# esquemacamiseta1.net
KiCad netlist of a schematic drawn in EAGLE
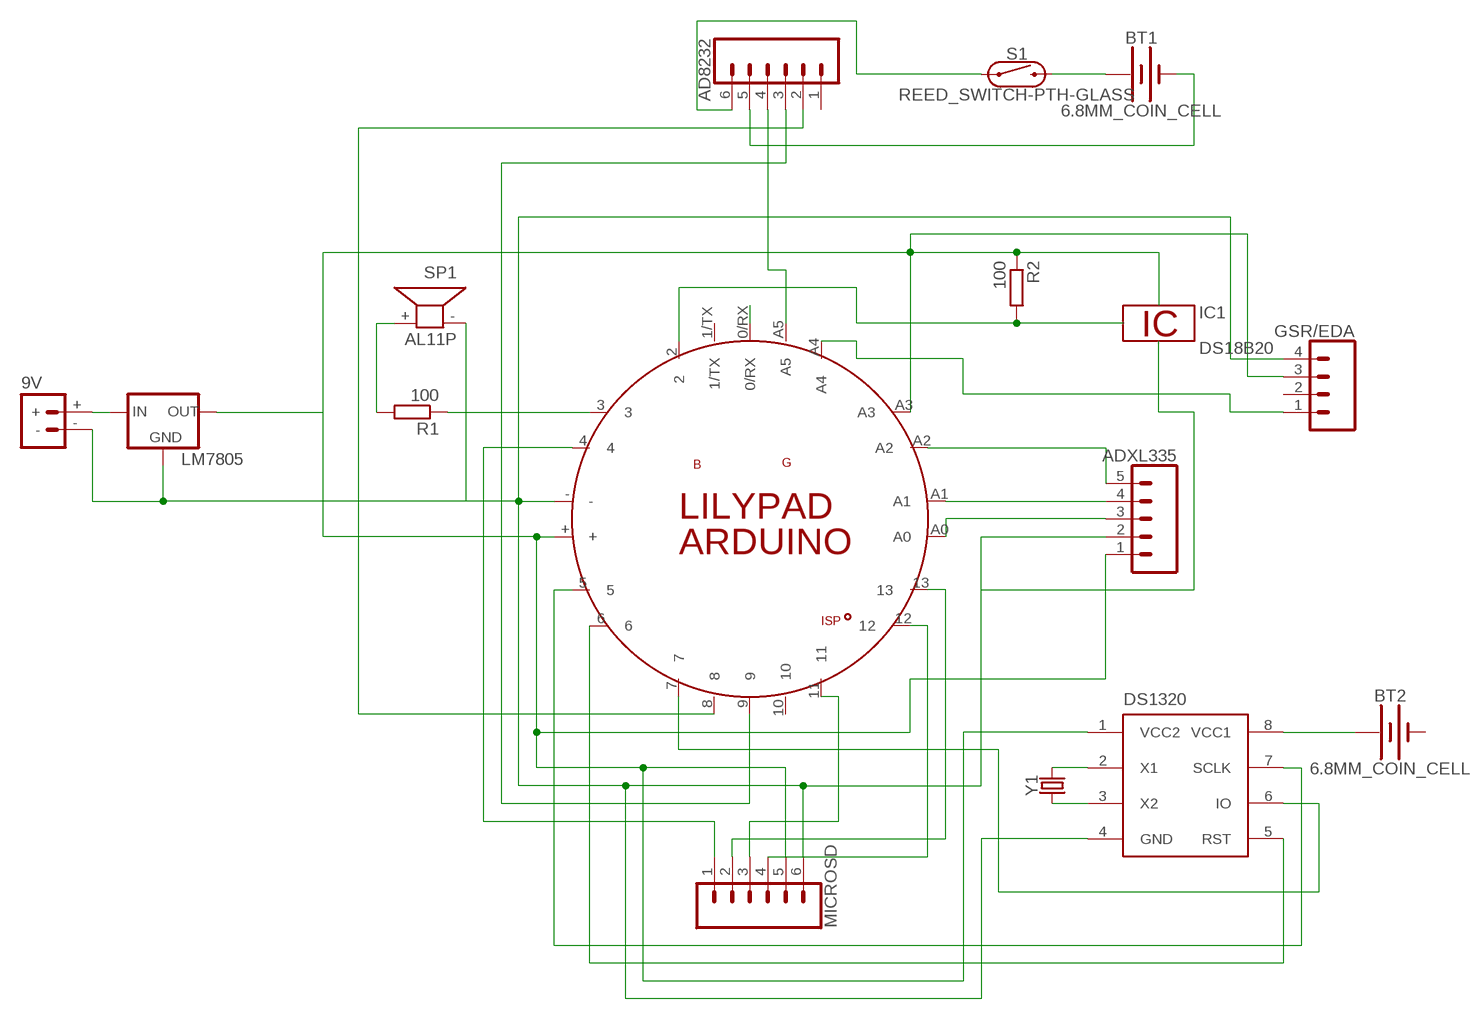
[diagram p0: schematic, sheet 1]

(export (version "E")
  (design (tool "Eeschema 10.0.6"))
  (components
    (comp (ref "9V")
      (value "BATTERY_CONN_DEANS")
      (footprint "eagle-import:DEANS")
      (libsource (lib "eagle-import") (part "BATTERY_CONN_DEANS"))
    )
    (comp (ref "AD8232")
      (value "CONN_06FEMALE_LOCK")
      (footprint "eagle-import:1X06_FEMALE_LOCK.010")
      (libsource (lib "eagle-import") (part "CONN_06FEMALE_LOCK"))
    )
    (comp (ref "ADXL335")
      (value "CONN_05")
      (footprint "eagle-import:1X05")
      (libsource (lib "eagle-import") (part "CONN_05"))
    )
    (comp (ref "BT1")
      (value "6.8MM_COIN_CELL")
      (footprint "eagle-import:BATTCON-6.8MM")
      (libsource (lib "eagle-import") (part "BATTERY-6.8MM_SMD"))
    )
    (comp (ref "BT2")
      (value "6.8MM_COIN_CELL")
      (footprint "eagle-import:BATTCON-6.8MM")
      (libsource (lib "eagle-import") (part "BATTERY-6.8MM_SMD"))
    )
    (comp (ref "DS1320")
      (value "DS1302")
      (footprint "eagle-import:PDIP8")
      (libsource (lib "eagle-import") (part "DS1302"))
    )
    (comp (ref "GSR/EDA")
      (value "CONN_04JST-PTH")
      (footprint "eagle-import:JST-4-PTH")
      (libsource (lib "eagle-import") (part "CONN_04JST-PTH"))
    )
    (comp (ref "IC1")
      (value "DS18B20")
      (footprint "eagle-import:TO92-")
      (libsource (lib "eagle-import") (part "DS18B20"))
    )
    (comp (ref "LM7805")
      (value "V_REG_78XX-TO-220")
      (footprint "eagle-import:TO-220-ALT")
      (libsource (lib "eagle-import") (part "V_REG_78XX-TO-220"))
    )
    (comp (ref "MICROSD")
      (value "CONN_06FEMALE_LOCK")
      (footprint "eagle-import:1X06_FEMALE_LOCK.010")
      (libsource (lib "eagle-import") (part "CONN_06FEMALE_LOCK"))
    )
    (comp (ref "PCB1")
      (value "ARDUINO_LILYPAD")
      (footprint "eagle-import:ARDUINO_LILYPAD")
      (libsource (lib "eagle-import") (part "ARDUINO_LILYPAD"))
    )
    (comp (ref "R1")
      (value "100")
      (footprint "eagle-import:0309_12")
      (libsource (lib "eagle-import") (part "R-EU_0309/12"))
    )
    (comp (ref "R2")
      (value "100")
      (footprint "eagle-import:0309_12")
      (libsource (lib "eagle-import") (part "R-EU_0309/12"))
    )
    (comp (ref "S1")
      (value "REED_SWITCH-PTH-GLASS")
      (footprint "eagle-import:REED_SWITCH_GLASS")
      (libsource (lib "eagle-import") (part "REED_SWITCH-PTH-GLASS"))
    )
    (comp (ref "SP1")
      (value "AL11P")
      (footprint "eagle-import:AL11P")
      (libsource (lib "eagle-import") (part "AL11P"))
    )
    (comp (ref "Y1")
      (value "CRYSTALPTH-2X6")
      (footprint "eagle-import:CRYSTAL-PTH-2X6-CYL")
      (libsource (lib "eagle-import") (part "CRYSTALPTH-2X6"))
    )
  )
  (nets
    (net (code "1") (name "/-") (class "Default")
      (node (ref "BT2") (pin "-") (pinfunction "-_-") (pintype "power_in"))
    )
    (net (code "2") (name "Net-(9V-Pad+)") (class "Default")
      (node (ref "9V") (pin "+") (pinfunction "+_+") (pintype "passive"))
      (node (ref "LM7805") (pin "IN") (pinfunction "IN_IN") (pintype "input"))
    )
    (net (code "3") (name "Net-(AD8232-Pad2)") (class "Default")
      (node (ref "AD8232") (pin "2") (pinfunction "2_2") (pintype "passive"))
      (node (ref "PCB1") (pin "8") (pinfunction "8_8") (pintype "bidirectional"))
    )
    (net (code "4") (name "Net-(AD8232-Pad3)") (class "Default")
      (node (ref "AD8232") (pin "3") (pinfunction "3_3") (pintype "passive"))
      (node (ref "PCB1") (pin "9") (pinfunction "9_9") (pintype "bidirectional"))
    )
    (net (code "5") (name "Net-(AD8232-Pad4)") (class "Default")
      (node (ref "AD8232") (pin "4") (pinfunction "4_4") (pintype "passive"))
      (node (ref "PCB1") (pin "A5") (pinfunction "A5_A5") (pintype "bidirectional"))
    )
    (net (code "6") (name "Net-(AD8232-Pad5)") (class "Default")
      (node (ref "AD8232") (pin "5") (pinfunction "5_5") (pintype "passive"))
      (node (ref "BT1") (pin "-") (pinfunction "-_-") (pintype "power_in"))
    )
    (net (code "7") (name "Net-(ADXL335-Pad3)") (class "Default")
      (node (ref "ADXL335") (pin "3") (pinfunction "3_3") (pintype "passive"))
      (node (ref "PCB1") (pin "A0") (pinfunction "A0_A0") (pintype "bidirectional"))
    )
    (net (code "8") (name "Net-(ADXL335-Pad4)") (class "Default")
      (node (ref "ADXL335") (pin "4") (pinfunction "4_4") (pintype "passive"))
      (node (ref "PCB1") (pin "A1") (pinfunction "A1_A1") (pintype "bidirectional"))
    )
    (net (code "9") (name "Net-(ADXL335-Pad5)") (class "Default")
      (node (ref "ADXL335") (pin "5") (pinfunction "5_5") (pintype "passive"))
      (node (ref "PCB1") (pin "A2") (pinfunction "A2_A2") (pintype "bidirectional"))
    )
    (net (code "10") (name "Net-(DS1320-GND)") (class "Default")
      (node (ref "9V") (pin "-") (pinfunction "-_-") (pintype "passive"))
      (node (ref "ADXL335") (pin "2") (pinfunction "2_2") (pintype "passive"))
      (node (ref "DS1320") (pin "4") (pinfunction "GND_4") (pintype "power_in"))
      (node (ref "GSR/EDA") (pin "4") (pinfunction "4_4") (pintype "passive"))
      (node (ref "LM7805") (pin "GND") (pinfunction "GND_GND") (pintype "input"))
      (node (ref "MICROSD") (pin "6") (pinfunction "6_6") (pintype "passive"))
      (node (ref "PCB1") (pin "-") (pinfunction "-_-") (pintype "bidirectional"))
      (node (ref "SP1") (pin "-") (pinfunction "1_-") (pintype "passive"))
    )
    (net (code "11") (name "Net-(DS1320-IO)") (class "Default")
      (node (ref "DS1320") (pin "6") (pinfunction "IO_6") (pintype "bidirectional"))
      (node (ref "PCB1") (pin "7") (pinfunction "7_7") (pintype "bidirectional"))
    )
    (net (code "12") (name "Net-(DS1320-RST)") (class "Default")
      (node (ref "DS1320") (pin "5") (pinfunction "RST_5") (pintype "input"))
      (node (ref "PCB1") (pin "6") (pinfunction "6_6") (pintype "bidirectional"))
    )
    (net (code "13") (name "Net-(DS1320-SCLK)") (class "Default")
      (node (ref "DS1320") (pin "7") (pinfunction "SCLK_7") (pintype "input"))
      (node (ref "PCB1") (pin "5") (pinfunction "5_5") (pintype "bidirectional"))
    )
    (net (code "14") (name "Net-(DS1320-VCC1)") (class "Default")
      (node (ref "BT2") (pin "+") (pinfunction "+_+") (pintype "power_in"))
      (node (ref "DS1320") (pin "8") (pinfunction "VCC1_8") (pintype "power_in"))
    )
    (net (code "15") (name "Net-(DS1320-VCC2)") (class "Default")
      (node (ref "ADXL335") (pin "1") (pinfunction "1_1") (pintype "passive"))
      (node (ref "DS1320") (pin "1") (pinfunction "VCC2_1") (pintype "power_in"))
      (node (ref "GSR/EDA") (pin "3") (pinfunction "3_3") (pintype "passive"))
      (node (ref "MICROSD") (pin "5") (pinfunction "5_5") (pintype "passive"))
      (node (ref "PCB1") (pin "+") (pinfunction "+_+") (pintype "bidirectional"))
      (node (ref "PCB1") (pin "A3") (pinfunction "A3_A3") (pintype "bidirectional"))
      (node (ref "R2") (pin "1") (pinfunction "1_1") (pintype "passive"))
    )
    (net (code "16") (name "Net-(DS1320-X1)") (class "Default")
      (node (ref "DS1320") (pin "2") (pinfunction "X1_2") (pintype "bidirectional"))
      (node (ref "Y1") (pin "2") (pinfunction "2_2") (pintype "passive"))
    )
    (net (code "17") (name "Net-(DS1320-X2)") (class "Default")
      (node (ref "DS1320") (pin "3") (pinfunction "X2_3") (pintype "bidirectional"))
      (node (ref "Y1") (pin "1") (pinfunction "1_1") (pintype "passive"))
    )
    (net (code "18") (name "Net-(GSR/EDA-Pad1)") (class "Default")
      (node (ref "GSR/EDA") (pin "1") (pinfunction "1_1") (pintype "passive"))
      (node (ref "PCB1") (pin "A4") (pinfunction "A4_A4") (pintype "bidirectional"))
    )
    (net (code "19") (name "Net-(MICROSD-Pad1)") (class "Default")
      (node (ref "MICROSD") (pin "1") (pinfunction "1_1") (pintype "passive"))
      (node (ref "PCB1") (pin "4") (pinfunction "4_4") (pintype "bidirectional"))
    )
    (net (code "20") (name "Net-(MICROSD-Pad2)") (class "Default")
      (node (ref "MICROSD") (pin "2") (pinfunction "2_2") (pintype "passive"))
      (node (ref "PCB1") (pin "13") (pinfunction "13_13") (pintype "bidirectional"))
    )
    (net (code "21") (name "Net-(MICROSD-Pad3)") (class "Default")
      (node (ref "MICROSD") (pin "3") (pinfunction "3_3") (pintype "passive"))
      (node (ref "PCB1") (pin "11") (pinfunction "11_11") (pintype "bidirectional"))
    )
    (net (code "22") (name "Net-(MICROSD-Pad4)") (class "Default")
      (node (ref "MICROSD") (pin "4") (pinfunction "4_4") (pintype "passive"))
      (node (ref "PCB1") (pin "12") (pinfunction "12_12") (pintype "bidirectional"))
    )
    (net (code "23") (name "Net-(PCB1-Pad2)") (class "Default")
      (node (ref "PCB1") (pin "2") (pinfunction "2_2") (pintype "bidirectional"))
      (node (ref "R2") (pin "2") (pinfunction "2_2") (pintype "passive"))
    )
    (net (code "24") (name "Net-(PCB1-Pad3)") (class "Default")
      (node (ref "PCB1") (pin "3") (pinfunction "3_3") (pintype "bidirectional"))
      (node (ref "R1") (pin "1") (pinfunction "1_1") (pintype "passive"))
    )
    (net (code "25") (name "Net-(S1-1)") (class "Default")
      (node (ref "AD8232") (pin "6") (pinfunction "6_6") (pintype "passive"))
      (node (ref "S1") (pin "P$1") (pinfunction "1_P$1") (pintype "passive"))
    )
    (net (code "26") (name "Net-(S1-2)") (class "Default")
      (node (ref "BT1") (pin "+") (pinfunction "+_+") (pintype "power_in"))
      (node (ref "S1") (pin "P$2") (pinfunction "2_P$2") (pintype "passive"))
    )
    (net (code "27") (name "Net-(SP1-2)") (class "Default")
      (node (ref "R1") (pin "2") (pinfunction "2_2") (pintype "passive"))
      (node (ref "SP1") (pin "+") (pinfunction "2_+") (pintype "passive"))
    )
    (net (code "28") (name "unconnected-(AD8232-Pad1)") (class "Default")
      (node (ref "AD8232") (pin "1") (pinfunction "1_1") (pintype "passive"))
    )
    (net (code "29") (name "unconnected-(GSR/EDA-Pad2)") (class "Default")
      (node (ref "GSR/EDA") (pin "2") (pinfunction "2_2") (pintype "passive"))
    )
    (net (code "30") (name "unconnected-(LM7805-PadOUT)") (class "Default")
      (node (ref "LM7805") (pin "OUT") (pinfunction "OUT_OUT") (pintype "passive"))
    )
    (net (code "31") (name "unconnected-(PCB1-GND-PadGND_)") (class "Default")
      (node (ref "PCB1") (pin "GND_") (pinfunction "GND_GND_") (pintype "bidirectional"))
    )
    (net (code "32") (name "unconnected-(PCB1-Pad0{slash}RX)") (class "Default")
      (node (ref "PCB1") (pin "0/RX") (pinfunction "0/RX_0/RX") (pintype "bidirectional"))
    )
    (net (code "33") (name "unconnected-(PCB1-Pad1{slash}TX)") (class "Default")
      (node (ref "PCB1") (pin "1/TX") (pinfunction "1/TX_1/TX") (pintype "bidirectional"))
    )
    (net (code "34") (name "unconnected-(PCB1-Pad10)") (class "Default")
      (node (ref "PCB1") (pin "10") (pinfunction "10_10") (pintype "bidirectional"))
    )
    (net (code "35") (name "unconnected-(PCB1-PadDTR)") (class "Default")
      (node (ref "PCB1") (pin "DTR") (pinfunction "DTR_DTR") (pintype "bidirectional"))
    )
    (net (code "36") (name "unconnected-(PCB1-PadGND.)") (class "Default")
      (node (ref "PCB1") (pin "GND.") (pinfunction "GND._GND.") (pintype "bidirectional"))
    )
    (net (code "37") (name "unconnected-(PCB1-PadGND..)") (class "Default")
      (node (ref "PCB1") (pin "GND..") (pinfunction "GND.._GND..") (pintype "bidirectional"))
    )
    (net (code "38") (name "unconnected-(PCB1-PadMISO)") (class "Default")
      (node (ref "PCB1") (pin "MISO") (pinfunction "MISO_MISO") (pintype "bidirectional"))
    )
    (net (code "39") (name "unconnected-(PCB1-PadMOSI)") (class "Default")
      (node (ref "PCB1") (pin "MOSI") (pinfunction "MOSI_MOSI") (pintype "bidirectional"))
    )
    (net (code "40") (name "unconnected-(PCB1-PadRXI)") (class "Default")
      (node (ref "PCB1") (pin "RXI") (pinfunction "RXI_RXI") (pintype "bidirectional"))
    )
    (net (code "41") (name "unconnected-(PCB1-PadSCK)") (class "Default")
      (node (ref "PCB1") (pin "SCK") (pinfunction "SCK_SCK") (pintype "bidirectional"))
    )
    (net (code "42") (name "unconnected-(PCB1-PadTXO)") (class "Default")
      (node (ref "PCB1") (pin "TXO") (pinfunction "TXO_TXO") (pintype "bidirectional"))
    )
    (net (code "43") (name "unconnected-(PCB1-PadVCC.)") (class "Default")
      (node (ref "PCB1") (pin "VCC.") (pinfunction "VCC._VCC.") (pintype "bidirectional"))
    )
    (net (code "44") (name "unconnected-(PCB1-RST-PadRESET..)") (class "Default")
      (node (ref "PCB1") (pin "RESET..") (pinfunction "RST_RESET..") (pintype "bidirectional"))
    )
    (net (code "45") (name "unconnected-(PCB1-VCC-Pad5V.)") (class "Default")
      (node (ref "PCB1") (pin "5V.") (pinfunction "VCC_5V.") (pintype "bidirectional"))
    )
  )
)
